# WiFiSensorII.net
KiCad netlist of a schematic drawn in EAGLE
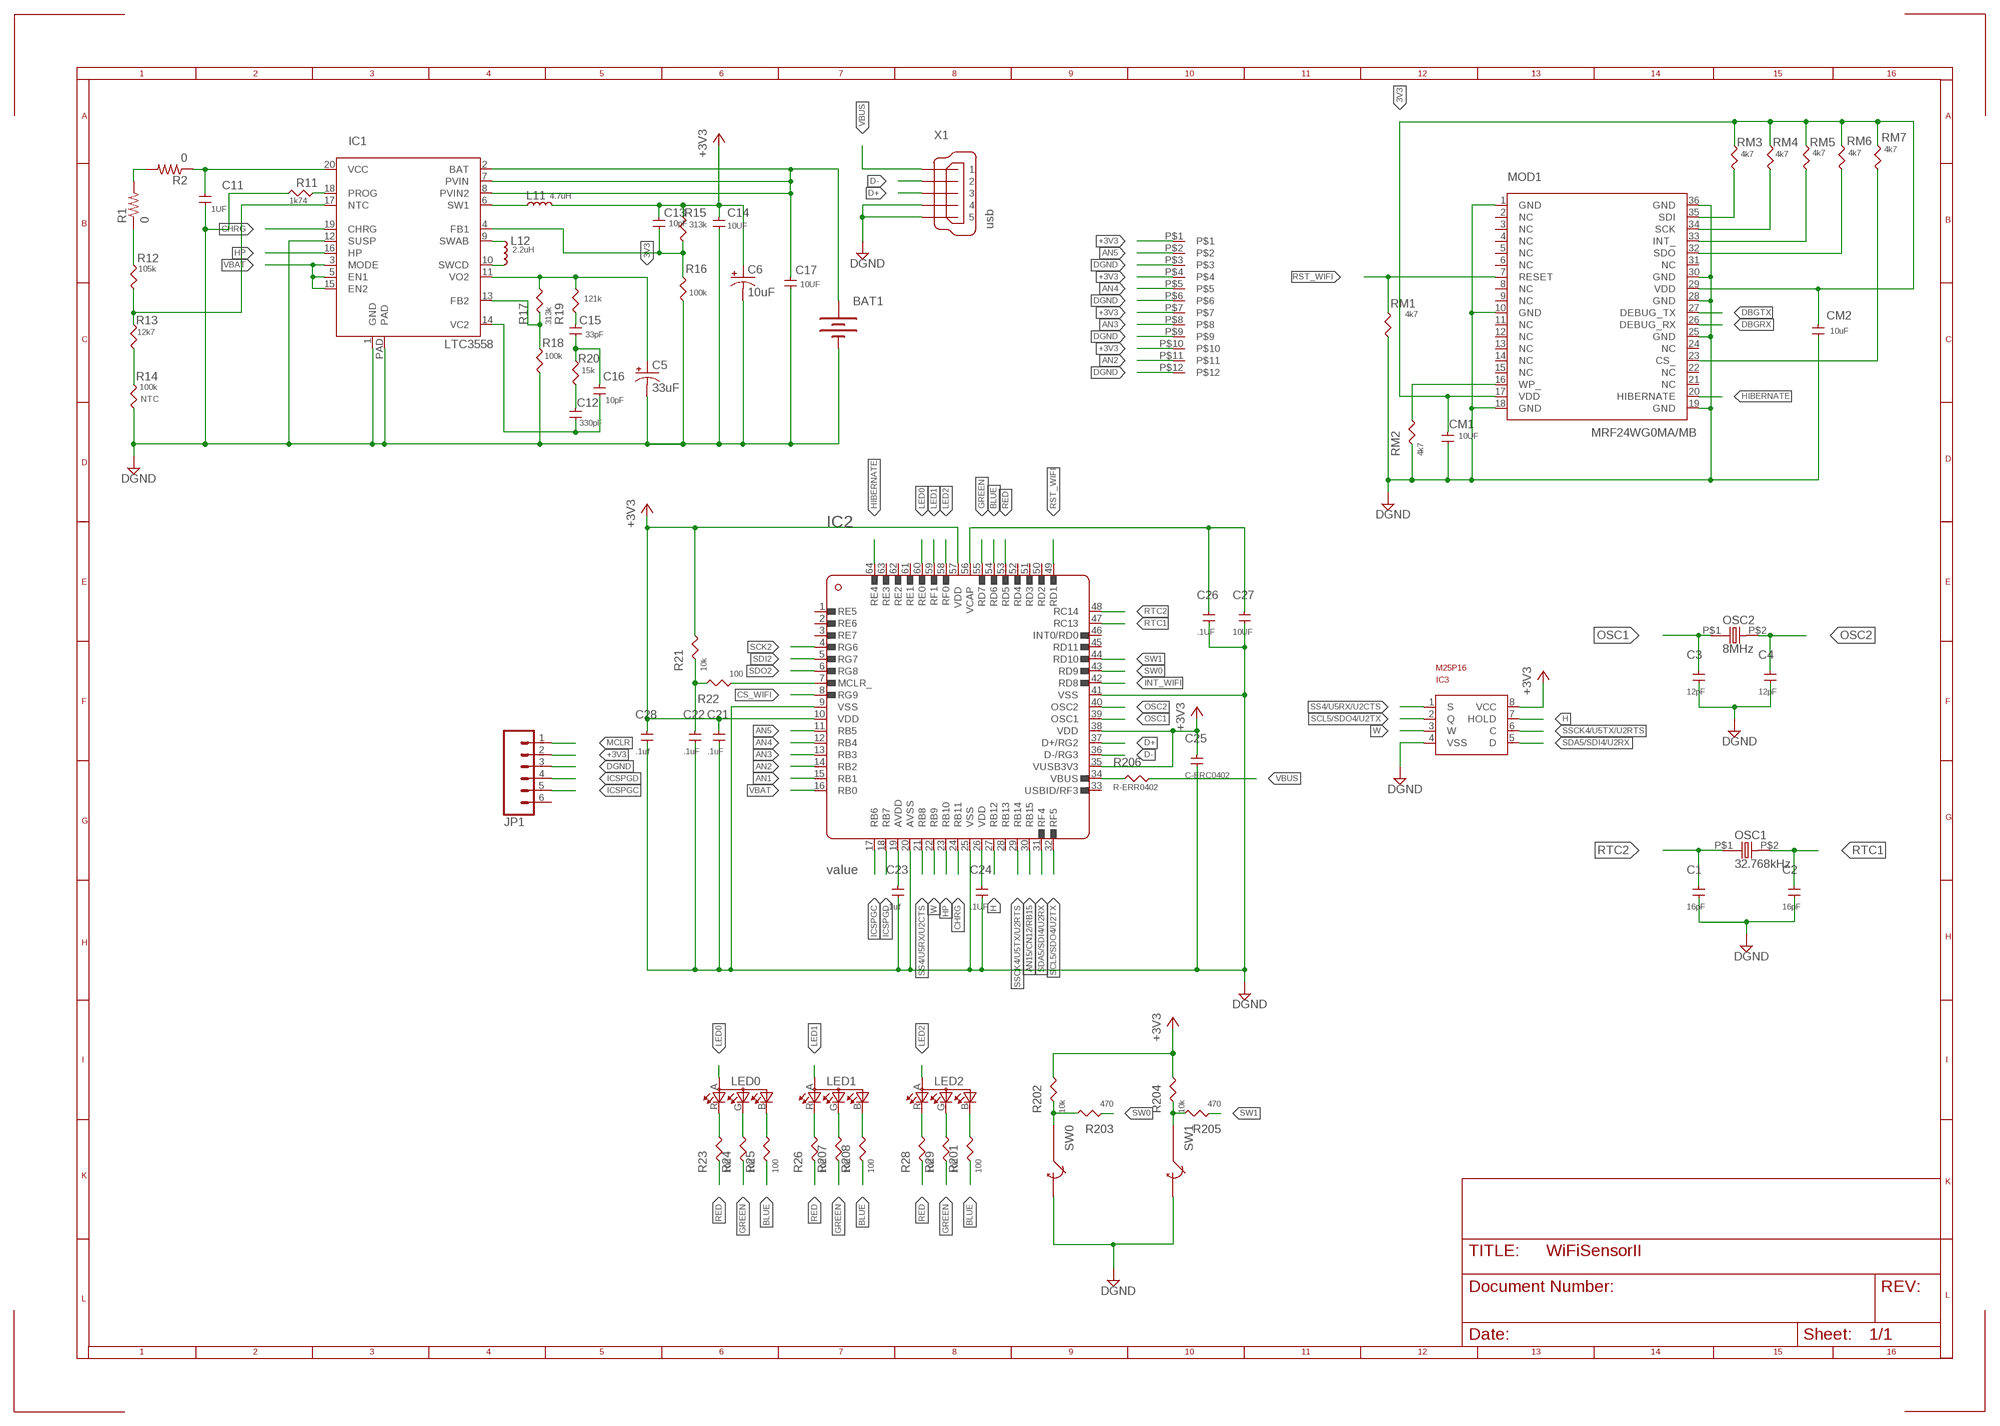
[diagram p0: schematic, sheet 1]

(export (version "E")
  (design (tool "Eeschema 10.0.6"))
  (components
    (comp (ref "BAT1")
      (value "BATTERY245PTH")
      (footprint "eagle-import:BATTCON_245MM_PTH")
      (libsource (lib "eagle-import") (part "BATTERY245PTH"))
    )
    (comp (ref "C1")
      (value "16pF")
      (footprint "eagle-import:C0402")
      (libsource (lib "eagle-import") (part "C-ERC0402"))
    )
    (comp (ref "C2")
      (value "16pF")
      (footprint "eagle-import:C0402")
      (libsource (lib "eagle-import") (part "C-ERC0402"))
    )
    (comp (ref "C3")
      (value "12pF")
      (footprint "eagle-import:C0402")
      (libsource (lib "eagle-import") (part "C-ERC0402"))
    )
    (comp (ref "C4")
      (value "12pF")
      (footprint "eagle-import:C0402")
      (libsource (lib "eagle-import") (part "C-ERC0402"))
    )
    (comp (ref "C5")
      (value "33uF")
      (footprint "eagle-import:PANASONIC_B")
      (libsource (lib "eagle-import") (part "CPOL-USB"))
    )
    (comp (ref "C6")
      (value "10uF")
      (footprint "eagle-import:PANASONIC_B")
      (libsource (lib "eagle-import") (part "CPOL-USB"))
    )
    (comp (ref "C11")
      (value "1UF")
      (footprint "eagle-import:C0402")
      (libsource (lib "eagle-import") (part "C-ERC0402"))
    )
    (comp (ref "C12")
      (value "330pF")
      (footprint "eagle-import:C0402")
      (libsource (lib "eagle-import") (part "C-ERC0402"))
    )
    (comp (ref "C13")
      (value "10pF")
      (footprint "eagle-import:C0402")
      (libsource (lib "eagle-import") (part "C-ERC0402"))
    )
    (comp (ref "C14")
      (value "10UF")
      (footprint "eagle-import:C0805")
      (libsource (lib "eagle-import") (part "C-ER"))
    )
    (comp (ref "C15")
      (value "33pF")
      (footprint "eagle-import:C0402")
      (libsource (lib "eagle-import") (part "C-ERC0402"))
    )
    (comp (ref "C16")
      (value "10pF")
      (footprint "eagle-import:C0402")
      (libsource (lib "eagle-import") (part "C-ERC0402"))
    )
    (comp (ref "C17")
      (value "10UF")
      (footprint "eagle-import:C0805")
      (libsource (lib "eagle-import") (part "C-ER"))
    )
    (comp (ref "C21")
      (value ".1uF")
      (footprint "eagle-import:C0402")
      (libsource (lib "eagle-import") (part "C-ERC0402"))
    )
    (comp (ref "C22")
      (value ".1uF")
      (footprint "eagle-import:C0402")
      (libsource (lib "eagle-import") (part "C-ERC0402"))
    )
    (comp (ref "C23")
      (value ".1uf")
      (footprint "eagle-import:C0402")
      (libsource (lib "eagle-import") (part "C-ERC0402"))
    )
    (comp (ref "C24")
      (value ".1UF")
      (footprint "eagle-import:C0402")
      (libsource (lib "eagle-import") (part "C-ERC0402"))
    )
    (comp (ref "C25")
      (value "C-ERC0402")
      (footprint "eagle-import:C0402")
      (libsource (lib "eagle-import") (part "C-ERC0402"))
    )
    (comp (ref "C26")
      (value ".1UF")
      (footprint "eagle-import:C0402")
      (libsource (lib "eagle-import") (part "C-ERC0402"))
    )
    (comp (ref "C27")
      (value "10UF")
      (footprint "eagle-import:C0805")
      (libsource (lib "eagle-import") (part "C-ER"))
    )
    (comp (ref "C28")
      (value ".1uf")
      (footprint "eagle-import:C0402")
      (libsource (lib "eagle-import") (part "C-ERC0402"))
    )
    (comp (ref "CM1")
      (value "10UF")
      (footprint "eagle-import:C0805")
      (libsource (lib "eagle-import") (part "C-ER"))
    )
    (comp (ref "CM2")
      (value "10uF")
      (footprint "eagle-import:C0805")
      (libsource (lib "eagle-import") (part "C-ER"))
    )
    (comp (ref "IC1")
      (value "LTC3558")
      (footprint "eagle-import:QFN20")
      (libsource (lib "eagle-import") (part "LTC3558"))
    )
    (comp (ref "IC2")
      (value "PICMX32695F512H")
      (footprint "eagle-import:TQFP64")
      (libsource (lib "eagle-import") (part "PICMX32695F512H"))
    )
    (comp (ref "IC3")
      (value "M25P16")
      (footprint "eagle-import:VDFPN8")
      (libsource (lib "eagle-import") (part "M25P16"))
    )
    (comp (ref "JP1")
      (value "M06LOCK")
      (footprint "eagle-import:1X06_LOCK")
      (libsource (lib "eagle-import") (part "M06LOCK"))
    )
    (comp (ref "L11")
      (value "4.7uH")
      (footprint "eagle-import:L3010")
      (libsource (lib "eagle-import") (part "L-ER"))
    )
    (comp (ref "L12")
      (value "2.2uH")
      (footprint "eagle-import:L3010")
      (libsource (lib "eagle-import") (part "L-ER"))
    )
    (comp (ref "LED0")
      (value "1X1RGB")
      (footprint "eagle-import:1X1")
      (libsource (lib "eagle-import") (part "1X1RGB"))
    )
    (comp (ref "LED1")
      (value "1X1RGB")
      (footprint "eagle-import:1X1")
      (libsource (lib "eagle-import") (part "1X1RGB"))
    )
    (comp (ref "LED2")
      (value "1X1RGB")
      (footprint "eagle-import:1X1")
      (libsource (lib "eagle-import") (part "1X1RGB"))
    )
    (comp (ref "MOD1")
      (value "MRF24WG0MA/MB")
      (footprint "eagle-import:MRF24")
      (libsource (lib "eagle-import") (part "MRF24WG0MA/MB"))
    )
    (comp (ref "OSC1")
      (value "32.768kHz")
      (footprint "eagle-import:ECX39")
      (fields (field (name "DIGIPART") "XC1658CT-ND"))
      (libsource (lib "eagle-import") (part "ECX32"))
    )
    (comp (ref "OSC2")
      (value "8MHz")
      (footprint "eagle-import:CX532")
      (fields (field (name "DIGIPART") "XC1658CT-ND"))
      (libsource (lib "eagle-import") (part "CX532"))
    )
    (comp (ref "R1")
      (value "0")
      (footprint "eagle-import:R1206")
      (libsource (lib "eagle-import") (part "R-US_R1206"))
    )
    (comp (ref "R2")
      (value "0")
      (footprint "eagle-import:R1206")
      (libsource (lib "eagle-import") (part "R-US_R1206"))
    )
    (comp (ref "R11")
      (value "1k74")
      (footprint "eagle-import:R0402")
      (libsource (lib "eagle-import") (part "R-ERR0402"))
    )
    (comp (ref "R12")
      (value "105k")
      (footprint "eagle-import:R0402")
      (libsource (lib "eagle-import") (part "R-ERR0402"))
    )
    (comp (ref "R13")
      (value "12k7")
      (footprint "eagle-import:R0402")
      (libsource (lib "eagle-import") (part "R-ERR0402"))
    )
    (comp (ref "R14")
      (value "100k")
      (footprint "eagle-import:R0402")
      (fields (field (name "NTC") "NTC"))
      (libsource (lib "eagle-import") (part "R-ERR0402"))
    )
    (comp (ref "R15")
      (value "313k")
      (footprint "eagle-import:R0402")
      (libsource (lib "eagle-import") (part "R-ERR0402"))
    )
    (comp (ref "R16")
      (value "100k")
      (footprint "eagle-import:R0402")
      (libsource (lib "eagle-import") (part "R-ERR0402"))
    )
    (comp (ref "R17")
      (value "313k")
      (footprint "eagle-import:R0402")
      (libsource (lib "eagle-import") (part "R-ERR0402"))
    )
    (comp (ref "R18")
      (value "100k")
      (footprint "eagle-import:R0402")
      (libsource (lib "eagle-import") (part "R-ERR0402"))
    )
    (comp (ref "R19")
      (value "121k")
      (footprint "eagle-import:R0402")
      (libsource (lib "eagle-import") (part "R-ERR0402"))
    )
    (comp (ref "R20")
      (value "15k")
      (footprint "eagle-import:R0402")
      (libsource (lib "eagle-import") (part "R-ERR0402"))
    )
    (comp (ref "R21")
      (value "10k")
      (footprint "eagle-import:R0402")
      (libsource (lib "eagle-import") (part "R-ERR0402"))
    )
    (comp (ref "R22")
      (value "100")
      (footprint "eagle-import:R0402")
      (libsource (lib "eagle-import") (part "R-ERR0402"))
    )
    (comp (ref "R23")
      (value "100")
      (footprint "eagle-import:R0402")
      (libsource (lib "eagle-import") (part "R-ERR0402"))
    )
    (comp (ref "R24")
      (value "100")
      (footprint "eagle-import:R0402")
      (libsource (lib "eagle-import") (part "R-ERR0402"))
    )
    (comp (ref "R25")
      (value "100")
      (footprint "eagle-import:R0402")
      (libsource (lib "eagle-import") (part "R-ERR0402"))
    )
    (comp (ref "R26")
      (value "100")
      (footprint "eagle-import:R0402")
      (libsource (lib "eagle-import") (part "R-ERR0402"))
    )
    (comp (ref "R28")
      (value "100")
      (footprint "eagle-import:R0402")
      (libsource (lib "eagle-import") (part "R-ERR0402"))
    )
    (comp (ref "R29")
      (value "100")
      (footprint "eagle-import:R0402")
      (libsource (lib "eagle-import") (part "R-ERR0402"))
    )
    (comp (ref "R201")
      (value "100")
      (footprint "eagle-import:R0402")
      (libsource (lib "eagle-import") (part "R-ERR0402"))
    )
    (comp (ref "R202")
      (value "10k")
      (footprint "eagle-import:R0402")
      (libsource (lib "eagle-import") (part "R-ERR0402"))
    )
    (comp (ref "R203")
      (value "470")
      (footprint "eagle-import:R0402")
      (libsource (lib "eagle-import") (part "R-ERR0402"))
    )
    (comp (ref "R204")
      (value "10k")
      (footprint "eagle-import:R0402")
      (libsource (lib "eagle-import") (part "R-ERR0402"))
    )
    (comp (ref "R205")
      (value "470")
      (footprint "eagle-import:R0402")
      (libsource (lib "eagle-import") (part "R-ERR0402"))
    )
    (comp (ref "R206")
      (value "R-ERR0402")
      (footprint "eagle-import:R0402")
      (libsource (lib "eagle-import") (part "R-ERR0402"))
    )
    (comp (ref "R207")
      (value "100")
      (footprint "eagle-import:R0402")
      (libsource (lib "eagle-import") (part "R-ERR0402"))
    )
    (comp (ref "R208")
      (value "100")
      (footprint "eagle-import:R0402")
      (libsource (lib "eagle-import") (part "R-ERR0402"))
    )
    (comp (ref "RM1")
      (value "4k7")
      (footprint "eagle-import:R0402")
      (libsource (lib "eagle-import") (part "R-ERR0402"))
    )
    (comp (ref "RM2")
      (value "4k7")
      (footprint "eagle-import:R0402")
      (libsource (lib "eagle-import") (part "R-ERR0402"))
    )
    (comp (ref "RM3")
      (value "4k7")
      (footprint "eagle-import:R0402")
      (libsource (lib "eagle-import") (part "R-ERR0402"))
    )
    (comp (ref "RM4")
      (value "4k7")
      (footprint "eagle-import:R0402")
      (libsource (lib "eagle-import") (part "R-ERR0402"))
    )
    (comp (ref "RM5")
      (value "4k7")
      (footprint "eagle-import:R0402")
      (libsource (lib "eagle-import") (part "R-ERR0402"))
    )
    (comp (ref "RM6")
      (value "4k7")
      (footprint "eagle-import:R0402")
      (libsource (lib "eagle-import") (part "R-ERR0402"))
    )
    (comp (ref "RM7")
      (value "4k7")
      (footprint "eagle-import:R0402")
      (libsource (lib "eagle-import") (part "R-ERR0402"))
    )
    (comp (ref "SW0")
      (value "BS3N")
      (footprint "eagle-import:BS3N")
      (libsource (lib "eagle-import") (part "BS3N"))
    )
    (comp (ref "SW1")
      (value "BS3N")
      (footprint "eagle-import:BS3N")
      (libsource (lib "eagle-import") (part "BS3N"))
    )
    (comp (ref "U$11")
      (value "12_127")
      (footprint "eagle-import:12-127")
      (libsource (lib "eagle-import") (part "12_127"))
    )
    (comp (ref "X1")
      (value "usb")
      (footprint "eagle-import:UX60A-MB-5ST")
      (libsource (lib "eagle-import") (part "MINI-USB-UX60A-MB-5ST"))
    )
  )
  (nets
    (net (code "1") (name "+3V3") (class "Default")
      (node (ref "C13") (pin "2") (pinfunction "P$2_2") (pintype "bidirectional"))
      (node (ref "C14") (pin "2") (pinfunction "P$2_2") (pintype "bidirectional"))
      (node (ref "C21") (pin "2") (pinfunction "P$2_2") (pintype "bidirectional"))
      (node (ref "C23") (pin "2") (pinfunction "P$2_2") (pintype "bidirectional"))
      (node (ref "C25") (pin "2") (pinfunction "P$2_2") (pintype "bidirectional"))
      (node (ref "C28") (pin "2") (pinfunction "P$2_2") (pintype "bidirectional"))
      (node (ref "C6") (pin "+") (pinfunction "+_+") (pintype "passive"))
      (node (ref "IC2") (pin "10") (pinfunction "VDD_10") (pintype "bidirectional"))
      (node (ref "IC2") (pin "19") (pinfunction "AVDD_19") (pintype "bidirectional"))
      (node (ref "IC2") (pin "35") (pinfunction "VUSB3V3_35") (pintype "bidirectional"))
      (node (ref "IC2") (pin "38") (pinfunction "VDD_38") (pintype "bidirectional"))
      (node (ref "IC2") (pin "57") (pinfunction "VDD_57") (pintype "bidirectional"))
      (node (ref "IC3") (pin "8") (pinfunction "VCC_8") (pintype "bidirectional"))
      (node (ref "JP1") (pin "2") (pinfunction "2_2") (pintype "passive"))
      (node (ref "L11") (pin "P$2") (pinfunction "P$2_P$2") (pintype "bidirectional"))
      (node (ref "R15") (pin "2") (pinfunction "P$2_2") (pintype "bidirectional"))
      (node (ref "R202") (pin "2") (pinfunction "P$2_2") (pintype "bidirectional"))
      (node (ref "R204") (pin "2") (pinfunction "P$2_2") (pintype "bidirectional"))
      (node (ref "R21") (pin "2") (pinfunction "P$2_2") (pintype "bidirectional"))
      (node (ref "U$11") (pin "P$1") (pinfunction "P$1_P$1") (pintype "bidirectional"))
      (node (ref "U$11") (pin "P$10") (pinfunction "P$10_P$10") (pintype "bidirectional"))
      (node (ref "U$11") (pin "P$4") (pinfunction "P$4_P$4") (pintype "bidirectional"))
      (node (ref "U$11") (pin "P$7") (pinfunction "P$7_P$7") (pintype "bidirectional"))
    )
    (net (code "2") (name "3V3") (class "Default")
      (node (ref "C5") (pin "+") (pinfunction "+_+") (pintype "passive"))
      (node (ref "CM1") (pin "2") (pinfunction "P$2_2") (pintype "bidirectional"))
      (node (ref "CM2") (pin "2") (pinfunction "P$2_2") (pintype "bidirectional"))
      (node (ref "IC1") (pin "11") (pinfunction "VO2_11") (pintype "bidirectional"))
      (node (ref "MOD1") (pin "17") (pinfunction "VDD_17") (pintype "bidirectional"))
      (node (ref "MOD1") (pin "29") (pinfunction "VDD_29") (pintype "bidirectional"))
      (node (ref "R17") (pin "2") (pinfunction "P$2_2") (pintype "bidirectional"))
      (node (ref "R19") (pin "2") (pinfunction "P$2_2") (pintype "bidirectional"))
      (node (ref "RM3") (pin "2") (pinfunction "P$2_2") (pintype "bidirectional"))
      (node (ref "RM4") (pin "2") (pinfunction "P$2_2") (pintype "bidirectional"))
      (node (ref "RM5") (pin "2") (pinfunction "P$2_2") (pintype "bidirectional"))
      (node (ref "RM6") (pin "2") (pinfunction "P$2_2") (pintype "bidirectional"))
      (node (ref "RM7") (pin "2") (pinfunction "P$2_2") (pintype "bidirectional"))
    )
    (net (code "3") (name "AN1") (class "Default")
      (node (ref "IC2") (pin "15") (pinfunction "RB1_15") (pintype "bidirectional"))
    )
    (net (code "4") (name "AN2") (class "Default")
      (node (ref "IC2") (pin "14") (pinfunction "RB2_14") (pintype "bidirectional"))
      (node (ref "U$11") (pin "P$11") (pinfunction "P$11_P$11") (pintype "bidirectional"))
    )
    (net (code "5") (name "AN3") (class "Default")
      (node (ref "IC2") (pin "13") (pinfunction "RB3_13") (pintype "bidirectional"))
      (node (ref "U$11") (pin "P$8") (pinfunction "P$8_P$8") (pintype "bidirectional"))
    )
    (net (code "6") (name "AN4") (class "Default")
      (node (ref "IC2") (pin "12") (pinfunction "RB4_12") (pintype "bidirectional"))
      (node (ref "U$11") (pin "P$5") (pinfunction "P$5_P$5") (pintype "bidirectional"))
    )
    (net (code "7") (name "AN5") (class "Default")
      (node (ref "IC2") (pin "11") (pinfunction "RB5_11") (pintype "bidirectional"))
      (node (ref "U$11") (pin "P$2") (pinfunction "P$2_P$2") (pintype "bidirectional"))
    )
    (net (code "8") (name "AN15{slash}CN12{slash}RB15") (class "Default")
      (node (ref "IC2") (pin "30") (pinfunction "RB15_30") (pintype "bidirectional"))
    )
    (net (code "9") (name "BLUE") (class "Default")
      (node (ref "IC2") (pin "54") (pinfunction "RD6_54") (pintype "bidirectional"))
      (node (ref "R201") (pin "1") (pinfunction "P$1_1") (pintype "bidirectional"))
      (node (ref "R208") (pin "1") (pinfunction "P$1_1") (pintype "bidirectional"))
      (node (ref "R25") (pin "1") (pinfunction "P$1_1") (pintype "bidirectional"))
    )
    (net (code "10") (name "CHRG") (class "Default")
      (node (ref "IC1") (pin "19") (pinfunction "CHRG_19") (pintype "bidirectional"))
      (node (ref "IC2") (pin "24") (pinfunction "RB11_24") (pintype "bidirectional"))
    )
    (net (code "11") (name "CS_WIFI") (class "Default")
      (node (ref "IC2") (pin "8") (pinfunction "RG9_8") (pintype "bidirectional"))
      (node (ref "MOD1") (pin "23") (pinfunction "CS__23") (pintype "bidirectional"))
      (node (ref "RM7") (pin "1") (pinfunction "P$1_1") (pintype "bidirectional"))
    )
    (net (code "12") (name "D+") (class "Default")
      (node (ref "IC2") (pin "37") (pinfunction "D+/RG2_37") (pintype "bidirectional"))
      (node (ref "X1") (pin "3") (pinfunction "3_3") (pintype "input"))
    )
    (net (code "13") (name "D-") (class "Default")
      (node (ref "IC2") (pin "36") (pinfunction "D-/RG3_36") (pintype "bidirectional"))
      (node (ref "X1") (pin "2") (pinfunction "2_2") (pintype "input"))
    )
    (net (code "14") (name "DBGRX") (class "Default")
      (node (ref "MOD1") (pin "26") (pinfunction "DEBUG_RX_26") (pintype "bidirectional"))
    )
    (net (code "15") (name "DBGTX") (class "Default")
      (node (ref "MOD1") (pin "27") (pinfunction "DEBUG_TX_27") (pintype "bidirectional"))
    )
    (net (code "16") (name "DGND") (class "Default")
      (node (ref "BAT1") (pin "2") (pinfunction "-_2") (pintype "power_in"))
      (node (ref "C1") (pin "1") (pinfunction "P$1_1") (pintype "bidirectional"))
      (node (ref "C11") (pin "1") (pinfunction "P$1_1") (pintype "bidirectional"))
      (node (ref "C14") (pin "1") (pinfunction "P$1_1") (pintype "bidirectional"))
      (node (ref "C17") (pin "1") (pinfunction "P$1_1") (pintype "bidirectional"))
      (node (ref "C2") (pin "1") (pinfunction "P$1_1") (pintype "bidirectional"))
      (node (ref "C21") (pin "1") (pinfunction "P$1_1") (pintype "bidirectional"))
      (node (ref "C22") (pin "1") (pinfunction "P$1_1") (pintype "bidirectional"))
      (node (ref "C23") (pin "1") (pinfunction "P$1_1") (pintype "bidirectional"))
      (node (ref "C24") (pin "1") (pinfunction "P$1_1") (pintype "bidirectional"))
      (node (ref "C25") (pin "1") (pinfunction "P$1_1") (pintype "bidirectional"))
      (node (ref "C26") (pin "1") (pinfunction "P$1_1") (pintype "bidirectional"))
      (node (ref "C27") (pin "1") (pinfunction "P$1_1") (pintype "bidirectional"))
      (node (ref "C28") (pin "1") (pinfunction "P$1_1") (pintype "bidirectional"))
      (node (ref "C3") (pin "1") (pinfunction "P$1_1") (pintype "bidirectional"))
      (node (ref "C4") (pin "1") (pinfunction "P$1_1") (pintype "bidirectional"))
      (node (ref "C5") (pin "-") (pinfunction "-_-") (pintype "passive"))
      (node (ref "C6") (pin "-") (pinfunction "-_-") (pintype "passive"))
      (node (ref "CM1") (pin "1") (pinfunction "P$1_1") (pintype "bidirectional"))
      (node (ref "CM2") (pin "1") (pinfunction "P$1_1") (pintype "bidirectional"))
      (node (ref "IC1") (pin "1") (pinfunction "GND_1") (pintype "bidirectional"))
      (node (ref "IC1") (pin "12") (pinfunction "SUSP_12") (pintype "bidirectional"))
      (node (ref "IC1") (pin "PAD") (pinfunction "PAD_PAD") (pintype "bidirectional"))
      (node (ref "IC2") (pin "20") (pinfunction "AVSS_20") (pintype "bidirectional"))
      (node (ref "IC2") (pin "25") (pinfunction "VSS_25") (pintype "bidirectional"))
      (node (ref "IC2") (pin "41") (pinfunction "VSS_41") (pintype "bidirectional"))
      (node (ref "IC2") (pin "9") (pinfunction "VSS_9") (pintype "bidirectional"))
      (node (ref "IC3") (pin "4") (pinfunction "VSS_4") (pintype "bidirectional"))
      (node (ref "JP1") (pin "3") (pinfunction "3_3") (pintype "passive"))
      (node (ref "MOD1") (pin "1") (pinfunction "GND_1") (pintype "bidirectional"))
      (node (ref "MOD1") (pin "10") (pinfunction "GND_10") (pintype "bidirectional"))
      (node (ref "MOD1") (pin "18") (pinfunction "GND_18") (pintype "bidirectional"))
      (node (ref "MOD1") (pin "19") (pinfunction "GND_19") (pintype "bidirectional"))
      (node (ref "MOD1") (pin "25") (pinfunction "GND_25") (pintype "bidirectional"))
      (node (ref "MOD1") (pin "28") (pinfunction "GND_28") (pintype "bidirectional"))
      (node (ref "MOD1") (pin "30") (pinfunction "GND_30") (pintype "bidirectional"))
      (node (ref "MOD1") (pin "36") (pinfunction "GND_36") (pintype "bidirectional"))
      (node (ref "R11") (pin "2") (pinfunction "P$2_2") (pintype "bidirectional"))
      (node (ref "R14") (pin "1") (pinfunction "P$1_1") (pintype "bidirectional"))
      (node (ref "R16") (pin "1") (pinfunction "P$1_1") (pintype "bidirectional"))
      (node (ref "R18") (pin "1") (pinfunction "P$1_1") (pintype "bidirectional"))
      (node (ref "RM1") (pin "1") (pinfunction "P$1_1") (pintype "bidirectional"))
      (node (ref "RM2") (pin "1") (pinfunction "P$1_1") (pintype "bidirectional"))
      (node (ref "SW0") (pin "2") (pinfunction "2_2") (pintype "bidirectional"))
      (node (ref "SW1") (pin "2") (pinfunction "2_2") (pintype "bidirectional"))
      (node (ref "U$11") (pin "P$12") (pinfunction "P$12_P$12") (pintype "bidirectional"))
      (node (ref "U$11") (pin "P$3") (pinfunction "P$3_P$3") (pintype "bidirectional"))
      (node (ref "U$11") (pin "P$6") (pinfunction "P$6_P$6") (pintype "bidirectional"))
      (node (ref "U$11") (pin "P$9") (pinfunction "P$9_P$9") (pintype "bidirectional"))
      (node (ref "X1") (pin "4") (pinfunction "4_4") (pintype "input"))
      (node (ref "X1") (pin "5") (pinfunction "5_5") (pintype "input"))
    )
    (net (code "17") (name "GREEN") (class "Default")
      (node (ref "IC2") (pin "55") (pinfunction "RD7_55") (pintype "bidirectional"))
      (node (ref "R207") (pin "1") (pinfunction "P$1_1") (pintype "bidirectional"))
      (node (ref "R24") (pin "1") (pinfunction "P$1_1") (pintype "bidirectional"))
      (node (ref "R29") (pin "1") (pinfunction "P$1_1") (pintype "bidirectional"))
    )
    (net (code "18") (name "H") (class "Default")
      (node (ref "IC2") (pin "27") (pinfunction "RB12_27") (pintype "bidirectional"))
      (node (ref "IC3") (pin "7") (pinfunction "HOLD_7") (pintype "bidirectional"))
    )
    (net (code "19") (name "HIBERNATE") (class "Default")
      (node (ref "IC2") (pin "64") (pinfunction "RE4_64") (pintype "bidirectional"))
      (node (ref "MOD1") (pin "20") (pinfunction "HIBERNATE_20") (pintype "bidirectional"))
    )
    (net (code "20") (name "HP") (class "Default")
      (node (ref "IC1") (pin "16") (pinfunction "HP_16") (pintype "bidirectional"))
      (node (ref "IC2") (pin "23") (pinfunction "RB10_23") (pintype "bidirectional"))
    )
    (net (code "21") (name "ICSPGC") (class "Default")
      (node (ref "IC2") (pin "17") (pinfunction "RB6_17") (pintype "bidirectional"))
      (node (ref "JP1") (pin "5") (pinfunction "5_5") (pintype "passive"))
    )
    (net (code "22") (name "ICSPGD") (class "Default")
      (node (ref "IC2") (pin "18") (pinfunction "RB7_18") (pintype "bidirectional"))
      (node (ref "JP1") (pin "4") (pinfunction "4_4") (pintype "passive"))
    )
    (net (code "23") (name "INT_WIFI") (class "Default")
      (node (ref "IC2") (pin "42") (pinfunction "RD8_42") (pintype "bidirectional"))
      (node (ref "MOD1") (pin "33") (pinfunction "INT__33") (pintype "bidirectional"))
      (node (ref "RM5") (pin "1") (pinfunction "P$1_1") (pintype "bidirectional"))
    )
    (net (code "24") (name "LED0") (class "Default")
      (node (ref "IC2") (pin "60") (pinfunction "RE0_60") (pintype "bidirectional"))
      (node (ref "LED0") (pin "A") (pinfunction "A2_A") (pintype "passive"))
    )
    (net (code "25") (name "LED1") (class "Default")
      (node (ref "IC2") (pin "59") (pinfunction "RF1_59") (pintype "bidirectional"))
      (node (ref "LED1") (pin "A") (pinfunction "A2_A") (pintype "passive"))
    )
    (net (code "26") (name "LED2") (class "Default")
      (node (ref "IC2") (pin "58") (pinfunction "RF0_58") (pintype "bidirectional"))
      (node (ref "LED2") (pin "A") (pinfunction "A2_A") (pintype "passive"))
    )
    (net (code "27") (name "MCLR") (class "Default")
      (node (ref "C22") (pin "2") (pinfunction "P$2_2") (pintype "bidirectional"))
      (node (ref "JP1") (pin "1") (pinfunction "1_1") (pintype "passive"))
      (node (ref "R21") (pin "1") (pinfunction "P$1_1") (pintype "bidirectional"))
      (node (ref "R22") (pin "2") (pinfunction "P$2_2") (pintype "bidirectional"))
    )
    (net (code "28") (name "Net-(C11-P$2)") (class "Default")
      (node (ref "C11") (pin "2") (pinfunction "P$2_2") (pintype "bidirectional"))
      (node (ref "IC1") (pin "20") (pinfunction "VCC_20") (pintype "bidirectional"))
      (node (ref "R2") (pin "1") (pinfunction "1_1") (pintype "passive"))
    )
    (net (code "29") (name "Net-(C12-P$1)") (class "Default")
      (node (ref "C12") (pin "1") (pinfunction "P$1_1") (pintype "bidirectional"))
      (node (ref "C16") (pin "1") (pinfunction "P$1_1") (pintype "bidirectional"))
      (node (ref "IC1") (pin "14") (pinfunction "VC2_14") (pintype "bidirectional"))
    )
    (net (code "30") (name "Net-(C12-P$2)") (class "Default")
      (node (ref "C12") (pin "2") (pinfunction "P$2_2") (pintype "bidirectional"))
      (node (ref "R20") (pin "1") (pinfunction "P$1_1") (pintype "bidirectional"))
    )
    (net (code "31") (name "Net-(C13-P$1)") (class "Default")
      (node (ref "C13") (pin "1") (pinfunction "P$1_1") (pintype "bidirectional"))
      (node (ref "IC1") (pin "4") (pinfunction "FB1_4") (pintype "bidirectional"))
      (node (ref "R15") (pin "1") (pinfunction "P$1_1") (pintype "bidirectional"))
      (node (ref "R16") (pin "2") (pinfunction "P$2_2") (pintype "bidirectional"))
    )
    (net (code "32") (name "Net-(C15-P$1)") (class "Default")
      (node (ref "C15") (pin "1") (pinfunction "P$1_1") (pintype "bidirectional"))
      (node (ref "C16") (pin "2") (pinfunction "P$2_2") (pintype "bidirectional"))
      (node (ref "R20") (pin "2") (pinfunction "P$2_2") (pintype "bidirectional"))
    )
    (net (code "33") (name "Net-(C15-P$2)") (class "Default")
      (node (ref "C15") (pin "2") (pinfunction "P$2_2") (pintype "bidirectional"))
      (node (ref "R19") (pin "1") (pinfunction "P$1_1") (pintype "bidirectional"))
    )
    (net (code "34") (name "Net-(C24-P$2)") (class "Default")
      (node (ref "C24") (pin "2") (pinfunction "P$2_2") (pintype "bidirectional"))
      (node (ref "IC2") (pin "26") (pinfunction "VDD_26") (pintype "bidirectional"))
    )
    (net (code "35") (name "Net-(C26-P$2)") (class "Default")
      (node (ref "C26") (pin "2") (pinfunction "P$2_2") (pintype "bidirectional"))
      (node (ref "C27") (pin "2") (pinfunction "P$2_2") (pintype "bidirectional"))
      (node (ref "IC2") (pin "56") (pinfunction "VCAP_56") (pintype "bidirectional"))
    )
    (net (code "36") (name "Net-(IC1-FB2)") (class "Default")
      (node (ref "IC1") (pin "13") (pinfunction "FB2_13") (pintype "bidirectional"))
      (node (ref "R17") (pin "1") (pinfunction "P$1_1") (pintype "bidirectional"))
      (node (ref "R18") (pin "2") (pinfunction "P$2_2") (pintype "bidirectional"))
    )
    (net (code "37") (name "Net-(IC1-NTC)") (class "Default")
      (node (ref "IC1") (pin "17") (pinfunction "NTC_17") (pintype "bidirectional"))
      (node (ref "R12") (pin "1") (pinfunction "P$1_1") (pintype "bidirectional"))
      (node (ref "R13") (pin "2") (pinfunction "P$2_2") (pintype "bidirectional"))
    )
    (net (code "38") (name "Net-(IC1-PROG)") (class "Default")
      (node (ref "IC1") (pin "18") (pinfunction "PROG_18") (pintype "bidirectional"))
      (node (ref "R11") (pin "1") (pinfunction "P$1_1") (pintype "bidirectional"))
    )
    (net (code "39") (name "Net-(IC1-SW1)") (class "Default")
      (node (ref "IC1") (pin "6") (pinfunction "SW1_6") (pintype "bidirectional"))
      (node (ref "L11") (pin "P$1") (pinfunction "P$1_P$1") (pintype "bidirectional"))
    )
    (net (code "40") (name "Net-(IC1-SWAB)") (class "Default")
      (node (ref "IC1") (pin "9") (pinfunction "SWAB_9") (pintype "bidirectional"))
      (node (ref "L12") (pin "P$1") (pinfunction "P$1_P$1") (pintype "bidirectional"))
    )
    (net (code "41") (name "Net-(IC1-SWCD)") (class "Default")
      (node (ref "IC1") (pin "10") (pinfunction "SWCD_10") (pintype "bidirectional"))
      (node (ref "L12") (pin "P$2") (pinfunction "P$2_P$2") (pintype "bidirectional"))
    )
    (net (code "42") (name "Net-(IC2-MCLR_)") (class "Default")
      (node (ref "IC2") (pin "7") (pinfunction "MCLR__7") (pintype "bidirectional"))
      (node (ref "R22") (pin "1") (pinfunction "P$1_1") (pintype "bidirectional"))
    )
    (net (code "43") (name "Net-(IC2-VBUS)") (class "Default")
      (node (ref "IC2") (pin "34") (pinfunction "VBUS_34") (pintype "bidirectional"))
      (node (ref "R206") (pin "1") (pinfunction "P$1_1") (pintype "bidirectional"))
    )
    (net (code "44") (name "Net-(LED0-CBLUE)") (class "Default")
      (node (ref "LED0") (pin "G") (pinfunction "CBLUE_G") (pintype "passive"))
      (node (ref "R24") (pin "2") (pinfunction "P$2_2") (pintype "bidirectional"))
    )
    (net (code "45") (name "Net-(LED0-CGREEN)") (class "Default")
      (node (ref "LED0") (pin "B") (pinfunction "CGREEN_B") (pintype "passive"))
      (node (ref "R25") (pin "2") (pinfunction "P$2_2") (pintype "bidirectional"))
    )
    (net (code "46") (name "Net-(LED0-CRED)") (class "Default")
      (node (ref "LED0") (pin "R") (pinfunction "CRED_R") (pintype "passive"))
      (node (ref "R23") (pin "2") (pinfunction "P$2_2") (pintype "bidirectional"))
    )
    (net (code "47") (name "Net-(LED1-CBLUE)") (class "Default")
      (node (ref "LED1") (pin "G") (pinfunction "CBLUE_G") (pintype "passive"))
      (node (ref "R207") (pin "2") (pinfunction "P$2_2") (pintype "bidirectional"))
    )
    (net (code "48") (name "Net-(LED1-CGREEN)") (class "Default")
      (node (ref "LED1") (pin "B") (pinfunction "CGREEN_B") (pintype "passive"))
      (node (ref "R208") (pin "2") (pinfunction "P$2_2") (pintype "bidirectional"))
    )
    (net (code "49") (name "Net-(LED1-CRED)") (class "Default")
      (node (ref "LED1") (pin "R") (pinfunction "CRED_R") (pintype "passive"))
      (node (ref "R26") (pin "2") (pinfunction "P$2_2") (pintype "bidirectional"))
    )
    (net (code "50") (name "Net-(LED2-CBLUE)") (class "Default")
      (node (ref "LED2") (pin "G") (pinfunction "CBLUE_G") (pintype "passive"))
      (node (ref "R29") (pin "2") (pinfunction "P$2_2") (pintype "bidirectional"))
    )
    (net (code "51") (name "Net-(LED2-CGREEN)") (class "Default")
      (node (ref "LED2") (pin "B") (pinfunction "CGREEN_B") (pintype "passive"))
      (node (ref "R201") (pin "2") (pinfunction "P$2_2") (pintype "bidirectional"))
    )
    (net (code "52") (name "Net-(LED2-CRED)") (class "Default")
      (node (ref "LED2") (pin "R") (pinfunction "CRED_R") (pintype "passive"))
      (node (ref "R28") (pin "2") (pinfunction "P$2_2") (pintype "bidirectional"))
    )
    (net (code "53") (name "Net-(MOD1-WP_)") (class "Default")
      (node (ref "MOD1") (pin "16") (pinfunction "WP__16") (pintype "bidirectional"))
      (node (ref "RM2") (pin "2") (pinfunction "P$2_2") (pintype "bidirectional"))
    )
    (net (code "54") (name "Net-(R12-P$2)") (class "Default")
      (node (ref "R1") (pin "1") (pinfunction "1_1") (pintype "passive"))
      (node (ref "R12") (pin "2") (pinfunction "P$2_2") (pintype "bidirectional"))
    )
    (net (code "55") (name "Net-(R13-P$1)") (class "Default")
      (node (ref "R13") (pin "1") (pinfunction "P$1_1") (pintype "bidirectional"))
      (node (ref "R14") (pin "2") (pinfunction "P$2_2") (pintype "bidirectional"))
    )
    (net (code "56") (name "Net-(R202-P$1)") (class "Default")
      (node (ref "R202") (pin "1") (pinfunction "P$1_1") (pintype "bidirectional"))
      (node (ref "R203") (pin "2") (pinfunction "P$2_2") (pintype "bidirectional"))
      (node (ref "SW0") (pin "1") (pinfunction "1_1") (pintype "bidirectional"))
    )
    (net (code "57") (name "Net-(R204-P$1)") (class "Default")
      (node (ref "R204") (pin "1") (pinfunction "P$1_1") (pintype "bidirectional"))
      (node (ref "R205") (pin "2") (pinfunction "P$2_2") (pintype "bidirectional"))
      (node (ref "SW1") (pin "1") (pinfunction "1_1") (pintype "bidirectional"))
    )
    (net (code "58") (name "OSC1") (class "Default")
      (node (ref "C3") (pin "2") (pinfunction "P$2_2") (pintype "bidirectional"))
      (node (ref "IC2") (pin "39") (pinfunction "OSC1_39") (pintype "bidirectional"))
      (node (ref "OSC2") (pin "P$1") (pinfunction "1_P$1") (pintype "passive"))
    )
    (net (code "59") (name "OSC2") (class "Default")
      (node (ref "C4") (pin "2") (pinfunction "P$2_2") (pintype "bidirectional"))
      (node (ref "IC2") (pin "40") (pinfunction "OSC2_40") (pintype "bidirectional"))
      (node (ref "OSC2") (pin "P$2") (pinfunction "2_P$2") (pintype "passive"))
    )
    (net (code "60") (name "RED") (class "Default")
      (node (ref "IC2") (pin "53") (pinfunction "RD5_53") (pintype "bidirectional"))
      (node (ref "R23") (pin "1") (pinfunction "P$1_1") (pintype "bidirectional"))
      (node (ref "R26") (pin "1") (pinfunction "P$1_1") (pintype "bidirectional"))
      (node (ref "R28") (pin "1") (pinfunction "P$1_1") (pintype "bidirectional"))
    )
    (net (code "61") (name "RST_WIFI") (class "Default")
      (node (ref "IC2") (pin "49") (pinfunction "RD1_49") (pintype "bidirectional"))
      (node (ref "MOD1") (pin "7") (pinfunction "RESET_7") (pintype "bidirectional"))
      (node (ref "RM1") (pin "2") (pinfunction "P$2_2") (pintype "bidirectional"))
    )
    (net (code "62") (name "RTC1") (class "Default")
      (node (ref "C2") (pin "2") (pinfunction "P$2_2") (pintype "bidirectional"))
      (node (ref "IC2") (pin "47") (pinfunction "RC13_47") (pintype "bidirectional"))
      (node (ref "OSC1") (pin "P$2") (pinfunction "2_P$2") (pintype "passive"))
    )
    (net (code "63") (name "RTC2") (class "Default")
      (node (ref "C1") (pin "2") (pinfunction "P$2_2") (pintype "bidirectional"))
      (node (ref "IC2") (pin "48") (pinfunction "RC14_48") (pintype "bidirectional"))
      (node (ref "OSC1") (pin "P$1") (pinfunction "1_P$1") (pintype "passive"))
    )
    (net (code "64") (name "SCK2") (class "Default")
      (node (ref "IC2") (pin "4") (pinfunction "RG6_4") (pintype "bidirectional"))
      (node (ref "MOD1") (pin "34") (pinfunction "SCK_34") (pintype "bidirectional"))
      (node (ref "RM4") (pin "1") (pinfunction "P$1_1") (pintype "bidirectional"))
    )
    (net (code "65") (name "SCL5{slash}SDO4{slash}U2TX") (class "Default")
      (node (ref "IC2") (pin "32") (pinfunction "RF5_32") (pintype "bidirectional"))
      (node (ref "IC3") (pin "2") (pinfunction "Q_2") (pintype "bidirectional"))
    )
    (net (code "66") (name "SDA5{slash}SDI4{slash}U2RX") (class "Default")
      (node (ref "IC2") (pin "31") (pinfunction "RF4_31") (pintype "bidirectional"))
      (node (ref "IC3") (pin "5") (pinfunction "D_5") (pintype "bidirectional"))
    )
    (net (code "67") (name "SDI2") (class "Default")
      (node (ref "IC2") (pin "5") (pinfunction "RG7_5") (pintype "bidirectional"))
      (node (ref "MOD1") (pin "32") (pinfunction "SDO_32") (pintype "bidirectional"))
      (node (ref "RM6") (pin "1") (pinfunction "P$1_1") (pintype "bidirectional"))
    )
    (net (code "68") (name "SDO2") (class "Default")
      (node (ref "IC2") (pin "6") (pinfunction "RG8_6") (pintype "bidirectional"))
      (node (ref "MOD1") (pin "35") (pinfunction "SDI_35") (pintype "bidirectional"))
      (node (ref "RM3") (pin "1") (pinfunction "P$1_1") (pintype "bidirectional"))
    )
    (net (code "69") (name "SS4{slash}U5RX{slash}U2CTS") (class "Default")
      (node (ref "IC2") (pin "21") (pinfunction "RB8_21") (pintype "bidirectional"))
      (node (ref "IC3") (pin "1") (pinfunction "S_1") (pintype "bidirectional"))
    )
    (net (code "70") (name "SSCK4{slash}U5TX{slash}U2RTS") (class "Default")
      (node (ref "IC2") (pin "29") (pinfunction "RB14_29") (pintype "bidirectional"))
      (node (ref "IC3") (pin "6") (pinfunction "C_6") (pintype "bidirectional"))
    )
    (net (code "71") (name "SW0") (class "Default")
      (node (ref "IC2") (pin "43") (pinfunction "RD9_43") (pintype "bidirectional"))
      (node (ref "R203") (pin "1") (pinfunction "P$1_1") (pintype "bidirectional"))
    )
    (net (code "72") (name "SW1") (class "Default")
      (node (ref "IC2") (pin "44") (pinfunction "RD10_44") (pintype "bidirectional"))
      (node (ref "R205") (pin "1") (pinfunction "P$1_1") (pintype "bidirectional"))
    )
    (net (code "73") (name "VBAT") (class "Default")
      (node (ref "BAT1") (pin "3") (pinfunction "+_3") (pintype "power_in"))
      (node (ref "C17") (pin "2") (pinfunction "P$2_2") (pintype "bidirectional"))
      (node (ref "IC1") (pin "15") (pinfunction "EN2_15") (pintype "bidirectional"))
      (node (ref "IC1") (pin "2") (pinfunction "BAT_2") (pintype "bidirectional"))
      (node (ref "IC1") (pin "3") (pinfunction "MODE_3") (pintype "bidirectional"))
      (node (ref "IC1") (pin "5") (pinfunction "EN1_5") (pintype "bidirectional"))
      (node (ref "IC1") (pin "7") (pinfunction "PVIN_7") (pintype "bidirectional"))
      (node (ref "IC1") (pin "8") (pinfunction "PVIN2_8") (pintype "bidirectional"))
      (node (ref "IC2") (pin "16") (pinfunction "RB0_16") (pintype "bidirectional"))
    )
    (net (code "74") (name "VBUS") (class "Default")
      (node (ref "R1") (pin "2") (pinfunction "2_2") (pintype "passive"))
      (node (ref "R2") (pin "2") (pinfunction "2_2") (pintype "passive"))
      (node (ref "R206") (pin "2") (pinfunction "P$2_2") (pintype "bidirectional"))
      (node (ref "X1") (pin "1") (pinfunction "1_1") (pintype "input"))
    )
    (net (code "75") (name "W") (class "Default")
      (node (ref "IC2") (pin "22") (pinfunction "RB9_22") (pintype "bidirectional"))
      (node (ref "IC3") (pin "3") (pinfunction "W_3") (pintype "bidirectional"))
    )
    (net (code "76") (name "unconnected-(IC2-INT0{slash}RD0-Pad46)") (class "Default")
      (node (ref "IC2") (pin "46") (pinfunction "INT0/RD0_46") (pintype "bidirectional"))
    )
    (net (code "77") (name "unconnected-(IC2-RB13-Pad28)") (class "Default")
      (node (ref "IC2") (pin "28") (pinfunction "RB13_28") (pintype "bidirectional"))
    )
    (net (code "78") (name "unconnected-(IC2-RD2-Pad50)") (class "Default")
      (node (ref "IC2") (pin "50") (pinfunction "RD2_50") (pintype "bidirectional"))
    )
    (net (code "79") (name "unconnected-(IC2-RD3-Pad51)") (class "Default")
      (node (ref "IC2") (pin "51") (pinfunction "RD3_51") (pintype "bidirectional"))
    )
    (net (code "80") (name "unconnected-(IC2-RD4-Pad52)") (class "Default")
      (node (ref "IC2") (pin "52") (pinfunction "RD4_52") (pintype "bidirectional"))
    )
    (net (code "81") (name "unconnected-(IC2-RD11-Pad45)") (class "Default")
      (node (ref "IC2") (pin "45") (pinfunction "RD11_45") (pintype "bidirectional"))
    )
    (net (code "82") (name "unconnected-(IC2-RE1-Pad61)") (class "Default")
      (node (ref "IC2") (pin "61") (pinfunction "RE1_61") (pintype "bidirectional"))
    )
    (net (code "83") (name "unconnected-(IC2-RE2-Pad62)") (class "Default")
      (node (ref "IC2") (pin "62") (pinfunction "RE2_62") (pintype "bidirectional"))
    )
    (net (code "84") (name "unconnected-(IC2-RE3-Pad63)") (class "Default")
      (node (ref "IC2") (pin "63") (pinfunction "RE3_63") (pintype "bidirectional"))
    )
    (net (code "85") (name "unconnected-(IC2-RE5-Pad1)") (class "Default")
      (node (ref "IC2") (pin "1") (pinfunction "RE5_1") (pintype "bidirectional"))
    )
    (net (code "86") (name "unconnected-(IC2-RE6-Pad2)") (class "Default")
      (node (ref "IC2") (pin "2") (pinfunction "RE6_2") (pintype "bidirectional"))
    )
    (net (code "87") (name "unconnected-(IC2-RE7-Pad3)") (class "Default")
      (node (ref "IC2") (pin "3") (pinfunction "RE7_3") (pintype "bidirectional"))
    )
    (net (code "88") (name "unconnected-(IC2-USBID{slash}RF3-Pad33)") (class "Default")
      (node (ref "IC2") (pin "33") (pinfunction "USBID/RF3_33") (pintype "bidirectional"))
    )
    (net (code "89") (name "unconnected-(JP1-Pad6)") (class "Default")
      (node (ref "JP1") (pin "6") (pinfunction "6_6") (pintype "passive"))
    )
    (net (code "90") (name "unconnected-(MOD1-NC-Pad2)") (class "Default")
      (node (ref "MOD1") (pin "2") (pinfunction "NC_2") (pintype "bidirectional"))
    )
    (net (code "91") (name "unconnected-(MOD1-NC-Pad3)") (class "Default")
      (node (ref "MOD1") (pin "3") (pinfunction "NC_3") (pintype "bidirectional"))
    )
    (net (code "92") (name "unconnected-(MOD1-NC-Pad4)") (class "Default")
      (node (ref "MOD1") (pin "4") (pinfunction "NC_4") (pintype "bidirectional"))
    )
    (net (code "93") (name "unconnected-(MOD1-NC-Pad5)") (class "Default")
      (node (ref "MOD1") (pin "5") (pinfunction "NC_5") (pintype "bidirectional"))
    )
    (net (code "94") (name "unconnected-(MOD1-NC-Pad6)") (class "Default")
      (node (ref "MOD1") (pin "6") (pinfunction "NC_6") (pintype "bidirectional"))
    )
    (net (code "95") (name "unconnected-(MOD1-NC-Pad8)") (class "Default")
      (node (ref "MOD1") (pin "8") (pinfunction "NC_8") (pintype "bidirectional"))
    )
    (net (code "96") (name "unconnected-(MOD1-NC-Pad9)") (class "Default")
      (node (ref "MOD1") (pin "9") (pinfunction "NC_9") (pintype "bidirectional"))
    )
    (net (code "97") (name "unconnected-(MOD1-NC-Pad11)") (class "Default")
      (node (ref "MOD1") (pin "11") (pinfunction "NC_11") (pintype "bidirectional"))
    )
    (net (code "98") (name "unconnected-(MOD1-NC-Pad12)") (class "Default")
      (node (ref "MOD1") (pin "12") (pinfunction "NC_12") (pintype "bidirectional"))
    )
    (net (code "99") (name "unconnected-(MOD1-NC-Pad13)") (class "Default")
      (node (ref "MOD1") (pin "13") (pinfunction "NC_13") (pintype "bidirectional"))
    )
    (net (code "100") (name "unconnected-(MOD1-NC-Pad14)") (class "Default")
      (node (ref "MOD1") (pin "14") (pinfunction "NC_14") (pintype "bidirectional"))
    )
    (net (code "101") (name "unconnected-(MOD1-NC-Pad15)") (class "Default")
      (node (ref "MOD1") (pin "15") (pinfunction "NC_15") (pintype "bidirectional"))
    )
    (net (code "102") (name "unconnected-(MOD1-NC-Pad21)") (class "Default")
      (node (ref "MOD1") (pin "21") (pinfunction "NC_21") (pintype "bidirectional"))
    )
    (net (code "103") (name "unconnected-(MOD1-NC-Pad22)") (class "Default")
      (node (ref "MOD1") (pin "22") (pinfunction "NC_22") (pintype "bidirectional"))
    )
    (net (code "104") (name "unconnected-(MOD1-NC-Pad24)") (class "Default")
      (node (ref "MOD1") (pin "24") (pinfunction "NC_24") (pintype "bidirectional"))
    )
    (net (code "105") (name "unconnected-(MOD1-NC-Pad31)") (class "Default")
      (node (ref "MOD1") (pin "31") (pinfunction "NC_31") (pintype "bidirectional"))
    )
  )
)
